# octanis_eps_revised.net
KiCad netlist of a schematic drawn in EAGLE
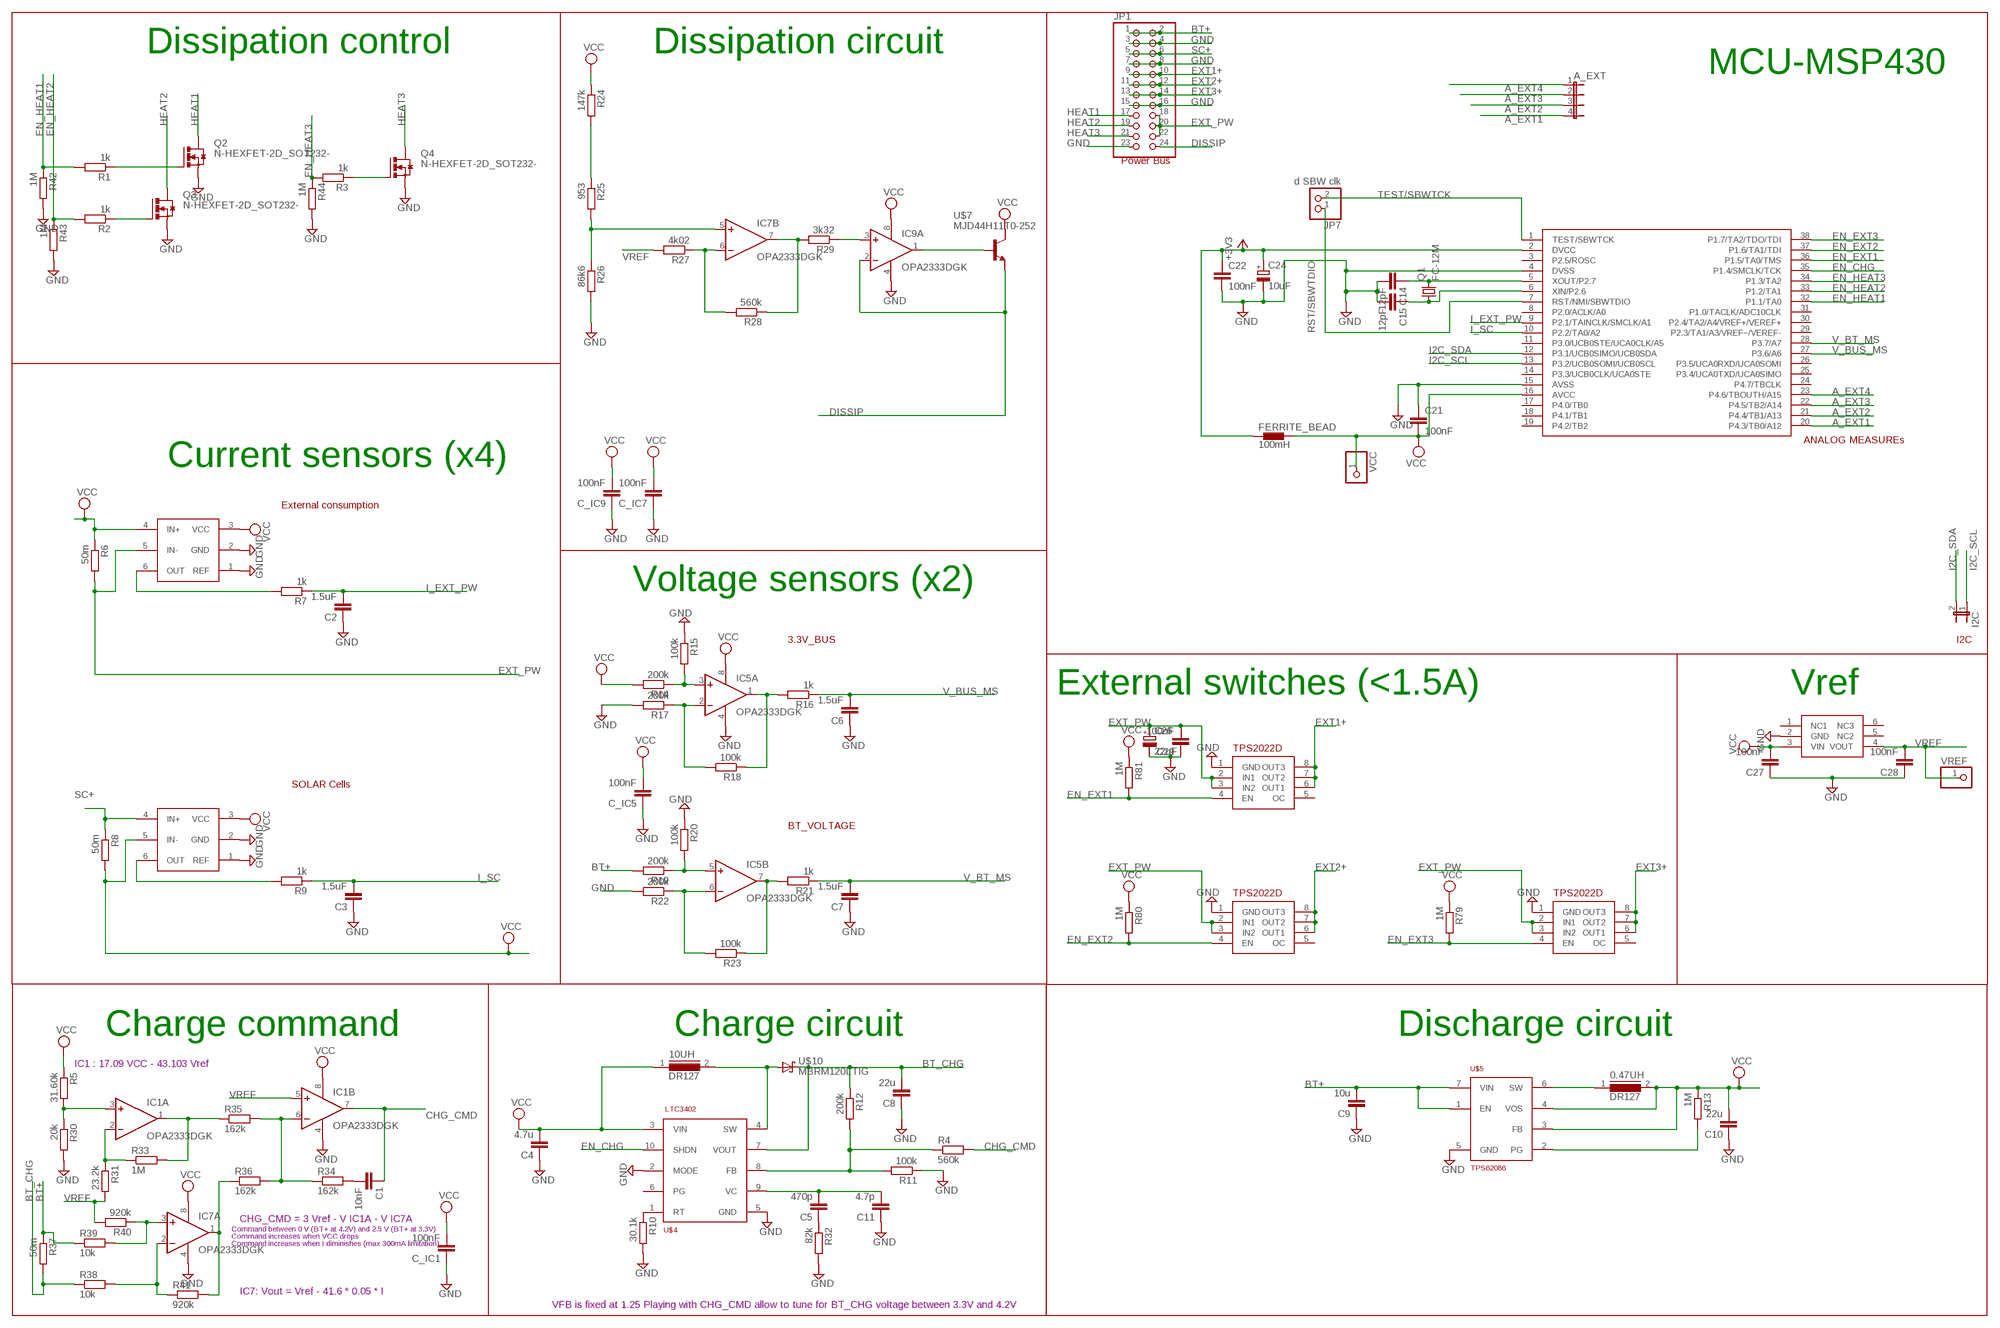
[diagram p0: schematic, sheet 1]

(export (version "E")
  (design (tool "Eeschema 10.0.6"))
  (components
    (comp (ref "0.47UH")
      (value "DR127")
      (footprint "eagle-import:DR127")
      (libsource (lib "eagle-import") (part "DR127"))
    )
    (comp (ref "10UH")
      (value "DR127")
      (footprint "eagle-import:DR127")
      (libsource (lib "eagle-import") (part "DR127"))
    )
    (comp (ref "A_EXT")
      (value "JP4E")
      (footprint "eagle-import:JP4")
      (libsource (lib "eagle-import") (part "JP4E"))
    )
    (comp (ref "C1")
      (value "10nF")
      (footprint "eagle-import:C0603")
      (libsource (lib "eagle-import") (part "C-EUC0603"))
    )
    (comp (ref "C2")
      (value "1.5uF")
      (footprint "eagle-import:C0603")
      (libsource (lib "eagle-import") (part "C-EUC0603"))
    )
    (comp (ref "C3")
      (value "1.5uF")
      (footprint "eagle-import:C0603")
      (libsource (lib "eagle-import") (part "C-EUC0603"))
    )
    (comp (ref "C4")
      (value "4.7u")
      (footprint "eagle-import:C1206")
      (libsource (lib "eagle-import") (part "C-EUC1206"))
    )
    (comp (ref "C5")
      (value "470p")
      (footprint "eagle-import:C0603")
      (libsource (lib "eagle-import") (part "C-EUC0603"))
    )
    (comp (ref "C6")
      (value "1.5uF")
      (footprint "eagle-import:C0603")
      (libsource (lib "eagle-import") (part "C-EUC0603"))
    )
    (comp (ref "C7")
      (value "1.5uF")
      (footprint "eagle-import:C0603")
      (libsource (lib "eagle-import") (part "C-EUC0603"))
    )
    (comp (ref "C8")
      (value "22u")
      (footprint "eagle-import:C0603")
      (libsource (lib "eagle-import") (part "C-EUC0603"))
    )
    (comp (ref "C9")
      (value "10u")
      (footprint "eagle-import:C1206")
      (libsource (lib "eagle-import") (part "C-EUC1206"))
    )
    (comp (ref "C10")
      (value "22u")
      (footprint "eagle-import:C1206")
      (libsource (lib "eagle-import") (part "C-EUC1206"))
    )
    (comp (ref "C11")
      (value "4.7p")
      (footprint "eagle-import:C0603")
      (libsource (lib "eagle-import") (part "C-EUC0603"))
    )
    (comp (ref "C14")
      (value "12pF")
      (footprint "eagle-import:C0603")
      (libsource (lib "eagle-import") (part "C-EUC0603"))
    )
    (comp (ref "C15")
      (value "12pF")
      (footprint "eagle-import:C0603")
      (libsource (lib "eagle-import") (part "C-EUC0603"))
    )
    (comp (ref "C21")
      (value "100nF")
      (footprint "eagle-import:C0603")
      (libsource (lib "eagle-import") (part "C-EUC0603"))
    )
    (comp (ref "C22")
      (value "100nF")
      (footprint "eagle-import:C0603")
      (libsource (lib "eagle-import") (part "C-EUC0603"))
    )
    (comp (ref "C24")
      (value "10uF")
      (footprint "eagle-import:A_3216-18R")
      (libsource (lib "eagle-import") (part "CPOL-EUA/3216-18R"))
    )
    (comp (ref "C26")
      (value "22uF")
      (footprint "eagle-import:A_3216-18R")
      (libsource (lib "eagle-import") (part "CPOL-EUA/3216-18R"))
    )
    (comp (ref "C27")
      (value "100nF")
      (footprint "eagle-import:C0603")
      (libsource (lib "eagle-import") (part "C-EUC0603"))
    )
    (comp (ref "C28")
      (value "100nF")
      (footprint "eagle-import:C0603")
      (libsource (lib "eagle-import") (part "C-EUC0603"))
    )
    (comp (ref "C29")
      (value "100nF")
      (footprint "eagle-import:C0603")
      (libsource (lib "eagle-import") (part "C-EUC0603"))
    )
    (comp (ref "C_IC1")
      (value "100nF")
      (footprint "eagle-import:C0603")
      (libsource (lib "eagle-import") (part "C-EUC0603"))
    )
    (comp (ref "C_IC5")
      (value "100nF")
      (footprint "eagle-import:C0603")
      (libsource (lib "eagle-import") (part "C-EUC0603"))
    )
    (comp (ref "C_IC7")
      (value "100nF")
      (footprint "eagle-import:C0603")
      (libsource (lib "eagle-import") (part "C-EUC0603"))
    )
    (comp (ref "C_IC9")
      (value "100nF")
      (footprint "eagle-import:C0603")
      (libsource (lib "eagle-import") (part "C-EUC0603"))
    )
    (comp (ref "FERRITE_BEAD")
      (value "100mH")
      (footprint "eagle-import:0402")
      (libsource (lib "eagle-import") (part "BLM15HD601SN1"))
    )
    (comp (ref "I2C")
      (value "JP1E")
      (footprint "eagle-import:JP1")
      (libsource (lib "eagle-import") (part "JP1E"))
    )
    (comp (ref "IC1")
      (value "OPA2333DGK")
      (footprint "eagle-import:MSOP08")
      (libsource (lib "eagle-import") (part "OPA2333DGK"))
    )
    (comp (ref "IC5")
      (value "OPA2333DGK")
      (footprint "eagle-import:MSOP08")
      (libsource (lib "eagle-import") (part "OPA2333DGK"))
    )
    (comp (ref "IC7")
      (value "OPA2333DGK")
      (footprint "eagle-import:MSOP08")
      (libsource (lib "eagle-import") (part "OPA2333DGK"))
    )
    (comp (ref "IC9")
      (value "OPA2333DGK")
      (footprint "eagle-import:MSOP08")
      (libsource (lib "eagle-import") (part "OPA2333DGK"))
    )
    (comp (ref "JP1")
      (value "PINHD-2X12")
      (footprint "eagle-import:2X12")
      (libsource (lib "eagle-import") (part "PINHD-2X12"))
    )
    (comp (ref "JP7")
      (value "d SBW clk")
      (footprint "eagle-import:1X02")
      (libsource (lib "eagle-import") (part "PINHD-1X2"))
    )
    (comp (ref "Q1")
      (value "FC-12M")
      (footprint "eagle-import:FC-12M")
      (libsource (lib "eagle-import") (part "FC-12M"))
    )
    (comp (ref "Q2")
      (value "N-HEXFET-2D_SOT232-")
      (footprint "eagle-import:SOT223")
      (libsource (lib "eagle-import") (part "N-HEXFET-2D_?-SOT232"))
    )
    (comp (ref "Q3")
      (value "N-HEXFET-2D_SOT232-")
      (footprint "eagle-import:SOT223")
      (libsource (lib "eagle-import") (part "N-HEXFET-2D_?-SOT232"))
    )
    (comp (ref "Q4")
      (value "N-HEXFET-2D_SOT232-")
      (footprint "eagle-import:SOT223")
      (libsource (lib "eagle-import") (part "N-HEXFET-2D_?-SOT232"))
    )
    (comp (ref "R1")
      (value "1k")
      (footprint "eagle-import:R0603")
      (libsource (lib "eagle-import") (part "R-EU_R0603"))
    )
    (comp (ref "R2")
      (value "1k")
      (footprint "eagle-import:R0603")
      (libsource (lib "eagle-import") (part "R-EU_R0603"))
    )
    (comp (ref "R3")
      (value "1k")
      (footprint "eagle-import:R0603")
      (libsource (lib "eagle-import") (part "R-EU_R0603"))
    )
    (comp (ref "R4")
      (value "560k")
      (footprint "eagle-import:R0603")
      (libsource (lib "eagle-import") (part "R-EU_R0603"))
    )
    (comp (ref "R5")
      (value "31.60k")
      (footprint "eagle-import:R0603")
      (libsource (lib "eagle-import") (part "R-EU_R0603"))
    )
    (comp (ref "R6")
      (value "50m")
      (footprint "eagle-import:R1206")
      (libsource (lib "eagle-import") (part "R-EU_R1206"))
    )
    (comp (ref "R7")
      (value "1k")
      (footprint "eagle-import:R0603")
      (libsource (lib "eagle-import") (part "R-EU_R0603"))
    )
    (comp (ref "R8")
      (value "50m")
      (footprint "eagle-import:R1206")
      (libsource (lib "eagle-import") (part "R-EU_R1206"))
    )
    (comp (ref "R9")
      (value "1k")
      (footprint "eagle-import:R0603")
      (libsource (lib "eagle-import") (part "R-EU_R0603"))
    )
    (comp (ref "R10")
      (value "30.1k")
      (footprint "eagle-import:R0603")
      (libsource (lib "eagle-import") (part "R-EU_R0603"))
    )
    (comp (ref "R11")
      (value "100k")
      (footprint "eagle-import:R0603")
      (libsource (lib "eagle-import") (part "R-EU_R0603"))
    )
    (comp (ref "R12")
      (value "200k")
      (footprint "eagle-import:R0603")
      (libsource (lib "eagle-import") (part "R-EU_R0603"))
    )
    (comp (ref "R13")
      (value "1M")
      (footprint "eagle-import:R0603")
      (libsource (lib "eagle-import") (part "R-EU_R0603"))
    )
    (comp (ref "R14")
      (value "200k")
      (footprint "eagle-import:R0603")
      (libsource (lib "eagle-import") (part "R-EU_R0603"))
    )
    (comp (ref "R15")
      (value "100k")
      (footprint "eagle-import:R0603")
      (libsource (lib "eagle-import") (part "R-EU_R0603"))
    )
    (comp (ref "R16")
      (value "1k")
      (footprint "eagle-import:R0603")
      (libsource (lib "eagle-import") (part "R-EU_R0603"))
    )
    (comp (ref "R17")
      (value "200k")
      (footprint "eagle-import:R0603")
      (libsource (lib "eagle-import") (part "R-EU_R0603"))
    )
    (comp (ref "R18")
      (value "100k")
      (footprint "eagle-import:R0603")
      (libsource (lib "eagle-import") (part "R-EU_R0603"))
    )
    (comp (ref "R19")
      (value "200k")
      (footprint "eagle-import:R0603")
      (libsource (lib "eagle-import") (part "R-EU_R0603"))
    )
    (comp (ref "R20")
      (value "100k")
      (footprint "eagle-import:R0603")
      (libsource (lib "eagle-import") (part "R-EU_R0603"))
    )
    (comp (ref "R21")
      (value "1k")
      (footprint "eagle-import:R0603")
      (libsource (lib "eagle-import") (part "R-EU_R0603"))
    )
    (comp (ref "R22")
      (value "200k")
      (footprint "eagle-import:R0603")
      (libsource (lib "eagle-import") (part "R-EU_R0603"))
    )
    (comp (ref "R23")
      (value "100k")
      (footprint "eagle-import:R0603")
      (libsource (lib "eagle-import") (part "R-EU_R0603"))
    )
    (comp (ref "R24")
      (value "147k")
      (footprint "eagle-import:R0603")
      (libsource (lib "eagle-import") (part "R-EU_R0603"))
    )
    (comp (ref "R25")
      (value "953")
      (footprint "eagle-import:R0603")
      (libsource (lib "eagle-import") (part "R-EU_R0603"))
    )
    (comp (ref "R26")
      (value "86k6")
      (footprint "eagle-import:R0603")
      (libsource (lib "eagle-import") (part "R-EU_R0603"))
    )
    (comp (ref "R27")
      (value "4k02")
      (footprint "eagle-import:R0603")
      (libsource (lib "eagle-import") (part "R-EU_R0603"))
    )
    (comp (ref "R28")
      (value "560k")
      (footprint "eagle-import:R0603")
      (libsource (lib "eagle-import") (part "R-EU_R0603"))
    )
    (comp (ref "R29")
      (value "3k32")
      (footprint "eagle-import:R0603")
      (libsource (lib "eagle-import") (part "R-EU_R0603"))
    )
    (comp (ref "R30")
      (value "20k")
      (footprint "eagle-import:R0603")
      (libsource (lib "eagle-import") (part "R-EU_R0603"))
    )
    (comp (ref "R31")
      (value "23.2k")
      (footprint "eagle-import:R0603")
      (libsource (lib "eagle-import") (part "R-EU_R0603"))
    )
    (comp (ref "R32")
      (value "82k")
      (footprint "eagle-import:R0603")
      (libsource (lib "eagle-import") (part "R-EU_R0603"))
    )
    (comp (ref "R33")
      (value "1M")
      (footprint "eagle-import:R0603")
      (libsource (lib "eagle-import") (part "R-EU_R0603"))
    )
    (comp (ref "R34")
      (value "162k")
      (footprint "eagle-import:R0603")
      (libsource (lib "eagle-import") (part "R-EU_R0603"))
    )
    (comp (ref "R35")
      (value "162k")
      (footprint "eagle-import:R0603")
      (libsource (lib "eagle-import") (part "R-EU_R0603"))
    )
    (comp (ref "R36")
      (value "162k")
      (footprint "eagle-import:R0603")
      (libsource (lib "eagle-import") (part "R-EU_R0603"))
    )
    (comp (ref "R37")
      (value "50m")
      (footprint "eagle-import:R1206")
      (libsource (lib "eagle-import") (part "R-EU_R1206"))
    )
    (comp (ref "R38")
      (value "10k")
      (footprint "eagle-import:R0603")
      (libsource (lib "eagle-import") (part "R-EU_R0603"))
    )
    (comp (ref "R39")
      (value "10k")
      (footprint "eagle-import:R0603")
      (libsource (lib "eagle-import") (part "R-EU_R0603"))
    )
    (comp (ref "R40")
      (value "920k")
      (footprint "eagle-import:R0603")
      (libsource (lib "eagle-import") (part "R-EU_R0603"))
    )
    (comp (ref "R41")
      (value "920k")
      (footprint "eagle-import:R0603")
      (libsource (lib "eagle-import") (part "R-EU_R0603"))
    )
    (comp (ref "R42")
      (value "1M")
      (footprint "eagle-import:R0603")
      (libsource (lib "eagle-import") (part "R-EU_R0603"))
    )
    (comp (ref "R43")
      (value "1M")
      (footprint "eagle-import:R0603")
      (libsource (lib "eagle-import") (part "R-EU_R0603"))
    )
    (comp (ref "R44")
      (value "1M")
      (footprint "eagle-import:R0603")
      (libsource (lib "eagle-import") (part "R-EU_R0603"))
    )
    (comp (ref "R79")
      (value "1M")
      (footprint "eagle-import:R0603")
      (libsource (lib "eagle-import") (part "R-EU_R0603"))
    )
    (comp (ref "R80")
      (value "1M")
      (footprint "eagle-import:R0603")
      (libsource (lib "eagle-import") (part "R-EU_R0603"))
    )
    (comp (ref "R81")
      (value "1M")
      (footprint "eagle-import:R0603")
      (libsource (lib "eagle-import") (part "R-EU_R0603"))
    )
    (comp (ref "U$2")
      (value "INA213")
      (footprint "eagle-import:SC70-6")
      (libsource (lib "eagle-import") (part "INA213"))
    )
    (comp (ref "U$3")
      (value "INA213")
      (footprint "eagle-import:SC70-6")
      (libsource (lib "eagle-import") (part "INA213"))
    )
    (comp (ref "U$4")
      (value "LTC3402")
      (footprint "eagle-import:MSOP10")
      (libsource (lib "eagle-import") (part "LTC3402"))
    )
    (comp (ref "U$5")
      (value "TPS62086")
      (footprint "eagle-import:QFN-7")
      (libsource (lib "eagle-import") (part "TPS62086"))
    )
    (comp (ref "U$6")
      (value "MSP430G2544")
      (footprint "eagle-import:TSSOP38")
      (libsource (lib "eagle-import") (part "MSP430G2544"))
    )
    (comp (ref "U$7")
      (value "MJD44H11T0-252")
      (footprint "eagle-import:TO252")
      (libsource (lib "eagle-import") (part "MJD44H11T0-252"))
    )
    (comp (ref "U$10")
      (value "MBRM120LTIG")
      (footprint "eagle-import:DO216AA")
      (libsource (lib "eagle-import") (part "MBRM120LTIG"))
    )
    (comp (ref "U$16")
      (value "TPS2022D")
      (footprint "eagle-import:SO8")
      (libsource (lib "eagle-import") (part "TPS2022D"))
    )
    (comp (ref "U$17")
      (value "TPS2022D")
      (footprint "eagle-import:SO8")
      (libsource (lib "eagle-import") (part "TPS2022D"))
    )
    (comp (ref "U$18")
      (value "TPS2022D")
      (footprint "eagle-import:SO8")
      (libsource (lib "eagle-import") (part "TPS2022D"))
    )
    (comp (ref "U$19")
      (value "ADR127B")
      (footprint "eagle-import:TSOT23-6")
      (libsource (lib "eagle-import") (part "ADR127B"))
    )
    (comp (ref "VCC")
      (value "PINHD-1X1")
      (footprint "eagle-import:1X01")
      (libsource (lib "eagle-import") (part "PINHD-1X1"))
    )
    (comp (ref "VREF")
      (value "PINHD-1X1")
      (footprint "eagle-import:1X01")
      (libsource (lib "eagle-import") (part "PINHD-1X1"))
    )
  )
  (nets
    (net (code "1") (name "+3V3") (class "Default")
      (node (ref "C22") (pin "1") (pinfunction "1_1") (pintype "passive"))
      (node (ref "C24") (pin "+") (pinfunction "+_+") (pintype "passive"))
      (node (ref "FERRITE_BEAD") (pin "1") (pinfunction "1_1") (pintype "passive"))
      (node (ref "U$6") (pin "2") (pinfunction "DVCC_2") (pintype "bidirectional"))
    )
    (net (code "2") (name "/A_EXT1") (class "Default")
      (node (ref "A_EXT") (pin "4") (pinfunction "4_4") (pintype "passive"))
      (node (ref "U$6") (pin "20") (pinfunction "P4.3/TB0/A12_20") (pintype "bidirectional"))
    )
    (net (code "3") (name "/A_EXT2") (class "Default")
      (node (ref "A_EXT") (pin "3") (pinfunction "3_3") (pintype "passive"))
      (node (ref "U$6") (pin "21") (pinfunction "P4.4/TB1/A13_21") (pintype "bidirectional"))
    )
    (net (code "4") (name "/A_EXT3") (class "Default")
      (node (ref "A_EXT") (pin "2") (pinfunction "2_2") (pintype "passive"))
      (node (ref "U$6") (pin "22") (pinfunction "P4.5/TB2/A14_22") (pintype "bidirectional"))
    )
    (net (code "5") (name "/A_EXT4") (class "Default")
      (node (ref "A_EXT") (pin "1") (pinfunction "1_1") (pintype "passive"))
      (node (ref "U$6") (pin "23") (pinfunction "P4.6/TBOUTH/A15_23") (pintype "bidirectional"))
    )
    (net (code "6") (name "/BT+") (class "Default")
      (node (ref "C9") (pin "2") (pinfunction "2_2") (pintype "passive"))
      (node (ref "JP1") (pin "1") (pinfunction "1_1") (pintype "passive"))
      (node (ref "JP1") (pin "2") (pinfunction "2_2") (pintype "passive"))
      (node (ref "R19") (pin "2") (pinfunction "2_2") (pintype "passive"))
      (node (ref "R37") (pin "1") (pinfunction "1_1") (pintype "passive"))
      (node (ref "R39") (pin "1") (pinfunction "1_1") (pintype "passive"))
      (node (ref "U$5") (pin "1") (pinfunction "EN_1") (pintype "bidirectional"))
      (node (ref "U$5") (pin "7") (pinfunction "VIN_7") (pintype "bidirectional"))
    )
    (net (code "7") (name "/BT_CHG") (class "Default")
      (node (ref "C8") (pin "2") (pinfunction "2_2") (pintype "passive"))
      (node (ref "R12") (pin "1") (pinfunction "1_1") (pintype "passive"))
      (node (ref "R37") (pin "2") (pinfunction "2_2") (pintype "passive"))
      (node (ref "R38") (pin "1") (pinfunction "1_1") (pintype "passive"))
      (node (ref "U$10") (pin "C") (pinfunction "K_C") (pintype "passive"))
      (node (ref "U$4") (pin "7") (pinfunction "VOUT_7") (pintype "bidirectional"))
    )
    (net (code "8") (name "/CHG_CMD") (class "Default")
      (node (ref "C1") (pin "1") (pinfunction "1_1") (pintype "passive"))
      (node (ref "IC1") (pin "7") (pinfunction "OUT_7") (pintype "output"))
      (node (ref "R4") (pin "2") (pinfunction "2_2") (pintype "passive"))
    )
    (net (code "9") (name "/DISSIP") (class "Default")
      (node (ref "IC9") (pin "2") (pinfunction "-IN_2") (pintype "input"))
      (node (ref "JP1") (pin "24") (pinfunction "24_24") (pintype "passive"))
      (node (ref "U$7") (pin "3") (pinfunction "E_3") (pintype "passive"))
    )
    (net (code "10") (name "/EN_CHG") (class "Default")
      (node (ref "U$4") (pin "10") (pinfunction "SHDN_10") (pintype "bidirectional"))
      (node (ref "U$6") (pin "35") (pinfunction "P1.4/SMCLK/TCK_35") (pintype "bidirectional"))
    )
    (net (code "11") (name "/EN_EXT1") (class "Default")
      (node (ref "R81") (pin "2") (pinfunction "2_2") (pintype "passive"))
      (node (ref "U$16") (pin "4") (pinfunction "EN_4") (pintype "bidirectional"))
      (node (ref "U$6") (pin "36") (pinfunction "P1.5/TA0/TMS_36") (pintype "bidirectional"))
    )
    (net (code "12") (name "/EN_EXT2") (class "Default")
      (node (ref "R80") (pin "2") (pinfunction "2_2") (pintype "passive"))
      (node (ref "U$17") (pin "4") (pinfunction "EN_4") (pintype "bidirectional"))
      (node (ref "U$6") (pin "37") (pinfunction "P1.6/TA1/TDI_37") (pintype "bidirectional"))
    )
    (net (code "13") (name "/EN_EXT3") (class "Default")
      (node (ref "R79") (pin "2") (pinfunction "2_2") (pintype "passive"))
      (node (ref "U$18") (pin "4") (pinfunction "EN_4") (pintype "bidirectional"))
      (node (ref "U$6") (pin "38") (pinfunction "P1.7/TA2/TDO/TDI_38") (pintype "bidirectional"))
    )
    (net (code "14") (name "/EN_HEAT1") (class "Default")
      (node (ref "R1") (pin "2") (pinfunction "2_2") (pintype "passive"))
      (node (ref "R42") (pin "1") (pinfunction "1_1") (pintype "passive"))
      (node (ref "U$6") (pin "32") (pinfunction "P1.1/TA0_32") (pintype "bidirectional"))
    )
    (net (code "15") (name "/EN_HEAT2") (class "Default")
      (node (ref "R2") (pin "2") (pinfunction "2_2") (pintype "passive"))
      (node (ref "R43") (pin "1") (pinfunction "1_1") (pintype "passive"))
      (node (ref "U$6") (pin "33") (pinfunction "P1.2/TA1_33") (pintype "bidirectional"))
    )
    (net (code "16") (name "/EN_HEAT3") (class "Default")
      (node (ref "R3") (pin "2") (pinfunction "2_2") (pintype "passive"))
      (node (ref "R44") (pin "1") (pinfunction "1_1") (pintype "passive"))
      (node (ref "U$6") (pin "34") (pinfunction "P1.3/TA2_34") (pintype "bidirectional"))
    )
    (net (code "17") (name "/EXT1+") (class "Default")
      (node (ref "JP1") (pin "10") (pinfunction "10_10") (pintype "passive"))
      (node (ref "JP1") (pin "9") (pinfunction "9_9") (pintype "passive"))
      (node (ref "U$16") (pin "6") (pinfunction "OUT1_6") (pintype "bidirectional"))
      (node (ref "U$16") (pin "7") (pinfunction "OUT2_7") (pintype "bidirectional"))
      (node (ref "U$16") (pin "8") (pinfunction "OUT3_8") (pintype "bidirectional"))
    )
    (net (code "18") (name "/EXT2+") (class "Default")
      (node (ref "JP1") (pin "11") (pinfunction "11_11") (pintype "passive"))
      (node (ref "JP1") (pin "12") (pinfunction "12_12") (pintype "passive"))
      (node (ref "U$17") (pin "6") (pinfunction "OUT1_6") (pintype "bidirectional"))
      (node (ref "U$17") (pin "7") (pinfunction "OUT2_7") (pintype "bidirectional"))
      (node (ref "U$17") (pin "8") (pinfunction "OUT3_8") (pintype "bidirectional"))
    )
    (net (code "19") (name "/EXT3+") (class "Default")
      (node (ref "JP1") (pin "13") (pinfunction "13_13") (pintype "passive"))
      (node (ref "JP1") (pin "14") (pinfunction "14_14") (pintype "passive"))
      (node (ref "U$18") (pin "6") (pinfunction "OUT1_6") (pintype "bidirectional"))
      (node (ref "U$18") (pin "7") (pinfunction "OUT2_7") (pintype "bidirectional"))
      (node (ref "U$18") (pin "8") (pinfunction "OUT3_8") (pintype "bidirectional"))
    )
    (net (code "20") (name "/EXT_PW") (class "Default")
      (node (ref "C26") (pin "+") (pinfunction "+_+") (pintype "passive"))
      (node (ref "C29") (pin "2") (pinfunction "2_2") (pintype "passive"))
      (node (ref "JP1") (pin "18") (pinfunction "18_18") (pintype "passive"))
      (node (ref "JP1") (pin "20") (pinfunction "20_20") (pintype "passive"))
      (node (ref "JP1") (pin "22") (pinfunction "22_22") (pintype "passive"))
      (node (ref "R6") (pin "2") (pinfunction "2_2") (pintype "passive"))
      (node (ref "U$16") (pin "2") (pinfunction "IN1_2") (pintype "bidirectional"))
      (node (ref "U$16") (pin "3") (pinfunction "IN2_3") (pintype "bidirectional"))
      (node (ref "U$17") (pin "2") (pinfunction "IN1_2") (pintype "bidirectional"))
      (node (ref "U$17") (pin "3") (pinfunction "IN2_3") (pintype "bidirectional"))
      (node (ref "U$18") (pin "2") (pinfunction "IN1_2") (pintype "bidirectional"))
      (node (ref "U$18") (pin "3") (pinfunction "IN2_3") (pintype "bidirectional"))
      (node (ref "U$2") (pin "5") (pinfunction "IN-_5") (pintype "bidirectional"))
    )
    (net (code "21") (name "/HEAT1") (class "Default")
      (node (ref "JP1") (pin "17") (pinfunction "17_17") (pintype "passive"))
      (node (ref "Q2") (pin "2") (pinfunction "D_2") (pintype "passive"))
      (node (ref "Q2") (pin "4") (pinfunction "D_4") (pintype "passive"))
    )
    (net (code "22") (name "/HEAT2") (class "Default")
      (node (ref "JP1") (pin "19") (pinfunction "19_19") (pintype "passive"))
      (node (ref "Q3") (pin "2") (pinfunction "D_2") (pintype "passive"))
      (node (ref "Q3") (pin "4") (pinfunction "D_4") (pintype "passive"))
    )
    (net (code "23") (name "/HEAT3") (class "Default")
      (node (ref "JP1") (pin "21") (pinfunction "21_21") (pintype "passive"))
      (node (ref "Q4") (pin "2") (pinfunction "D_2") (pintype "passive"))
      (node (ref "Q4") (pin "4") (pinfunction "D_4") (pintype "passive"))
    )
    (net (code "24") (name "/I2C_SCL") (class "Default")
      (node (ref "I2C") (pin "1") (pinfunction "1_1") (pintype "passive"))
      (node (ref "U$6") (pin "13") (pinfunction "P3.2/UCB0SOMI/UCB0SCL_13") (pintype "bidirectional"))
    )
    (net (code "25") (name "/I2C_SDA") (class "Default")
      (node (ref "I2C") (pin "2") (pinfunction "2_2") (pintype "passive"))
      (node (ref "U$6") (pin "12") (pinfunction "P3.1/UCB0SIMO/UCB0SDA_12") (pintype "bidirectional"))
    )
    (net (code "26") (name "/I_EXT_PW") (class "Default")
      (node (ref "C2") (pin "2") (pinfunction "2_2") (pintype "passive"))
      (node (ref "R7") (pin "1") (pinfunction "1_1") (pintype "passive"))
      (node (ref "U$6") (pin "9") (pinfunction "P2.1/TAINCLK/SMCLK/A1_9") (pintype "bidirectional"))
    )
    (net (code "27") (name "/I_SC") (class "Default")
      (node (ref "C3") (pin "2") (pinfunction "2_2") (pintype "passive"))
      (node (ref "R9") (pin "1") (pinfunction "1_1") (pintype "passive"))
      (node (ref "U$6") (pin "10") (pinfunction "P2.2/TA0/A2_10") (pintype "bidirectional"))
    )
    (net (code "28") (name "/RST{slash}SBWTDIO") (class "Default")
      (node (ref "JP7") (pin "1") (pinfunction "1_1") (pintype "passive"))
      (node (ref "U$6") (pin "7") (pinfunction "RST/NMI/SBWTDIO_7") (pintype "bidirectional"))
    )
    (net (code "29") (name "/SC+") (class "Default")
      (node (ref "JP1") (pin "5") (pinfunction "5_5") (pintype "passive"))
      (node (ref "JP1") (pin "6") (pinfunction "6_6") (pintype "passive"))
      (node (ref "R8") (pin "1") (pinfunction "1_1") (pintype "passive"))
      (node (ref "U$3") (pin "4") (pinfunction "IN+_4") (pintype "bidirectional"))
    )
    (net (code "30") (name "/TEST{slash}SBWTCK") (class "Default")
      (node (ref "JP7") (pin "2") (pinfunction "2_2") (pintype "passive"))
      (node (ref "U$6") (pin "1") (pinfunction "TEST/SBWTCK_1") (pintype "bidirectional"))
    )
    (net (code "31") (name "/VREF") (class "Default")
      (node (ref "C28") (pin "2") (pinfunction "2_2") (pintype "passive"))
      (node (ref "IC1") (pin "5") (pinfunction "+IN_5") (pintype "input"))
      (node (ref "R27") (pin "2") (pinfunction "2_2") (pintype "passive"))
      (node (ref "R31") (pin "2") (pinfunction "2_2") (pintype "passive"))
      (node (ref "R40") (pin "2") (pinfunction "2_2") (pintype "passive"))
      (node (ref "U$19") (pin "4") (pinfunction "VOUT_4") (pintype "bidirectional"))
      (node (ref "VREF") (pin "1") (pinfunction "1_1") (pintype "passive"))
    )
    (net (code "32") (name "/V_BT_MS") (class "Default")
      (node (ref "C7") (pin "2") (pinfunction "2_2") (pintype "passive"))
      (node (ref "R21") (pin "1") (pinfunction "1_1") (pintype "passive"))
      (node (ref "U$6") (pin "28") (pinfunction "P3.7/A7_28") (pintype "bidirectional"))
    )
    (net (code "33") (name "/V_BUS_MS") (class "Default")
      (node (ref "C6") (pin "2") (pinfunction "2_2") (pintype "passive"))
      (node (ref "R16") (pin "1") (pinfunction "1_1") (pintype "passive"))
      (node (ref "U$6") (pin "27") (pinfunction "P3.6/A6_27") (pintype "bidirectional"))
    )
    (net (code "34") (name "GND") (class "Default")
      (node (ref "C10") (pin "1") (pinfunction "1_1") (pintype "passive"))
      (node (ref "C11") (pin "1") (pinfunction "1_1") (pintype "passive"))
      (node (ref "C14") (pin "2") (pinfunction "2_2") (pintype "passive"))
      (node (ref "C15") (pin "2") (pinfunction "2_2") (pintype "passive"))
      (node (ref "C2") (pin "1") (pinfunction "1_1") (pintype "passive"))
      (node (ref "C21") (pin "1") (pinfunction "1_1") (pintype "passive"))
      (node (ref "C22") (pin "2") (pinfunction "2_2") (pintype "passive"))
      (node (ref "C24") (pin "-") (pinfunction "-_-") (pintype "passive"))
      (node (ref "C26") (pin "-") (pinfunction "-_-") (pintype "passive"))
      (node (ref "C27") (pin "1") (pinfunction "1_1") (pintype "passive"))
      (node (ref "C28") (pin "1") (pinfunction "1_1") (pintype "passive"))
      (node (ref "C29") (pin "1") (pinfunction "1_1") (pintype "passive"))
      (node (ref "C3") (pin "1") (pinfunction "1_1") (pintype "passive"))
      (node (ref "C4") (pin "1") (pinfunction "1_1") (pintype "passive"))
      (node (ref "C6") (pin "1") (pinfunction "1_1") (pintype "passive"))
      (node (ref "C7") (pin "1") (pinfunction "1_1") (pintype "passive"))
      (node (ref "C8") (pin "1") (pinfunction "1_1") (pintype "passive"))
      (node (ref "C9") (pin "1") (pinfunction "1_1") (pintype "passive"))
      (node (ref "C_IC1") (pin "1") (pinfunction "1_1") (pintype "passive"))
      (node (ref "C_IC5") (pin "1") (pinfunction "1_1") (pintype "passive"))
      (node (ref "C_IC7") (pin "1") (pinfunction "1_1") (pintype "passive"))
      (node (ref "C_IC9") (pin "1") (pinfunction "1_1") (pintype "passive"))
      (node (ref "IC1") (pin "4") (pinfunction "V-_4") (pintype "power_in"))
      (node (ref "IC5") (pin "4") (pinfunction "V-_4") (pintype "power_in"))
      (node (ref "IC7") (pin "4") (pinfunction "V-_4") (pintype "power_in"))
      (node (ref "IC9") (pin "4") (pinfunction "V-_4") (pintype "power_in"))
      (node (ref "JP1") (pin "15") (pinfunction "15_15") (pintype "passive"))
      (node (ref "JP1") (pin "16") (pinfunction "16_16") (pintype "passive"))
      (node (ref "JP1") (pin "23") (pinfunction "23_23") (pintype "passive"))
      (node (ref "JP1") (pin "3") (pinfunction "3_3") (pintype "passive"))
      (node (ref "JP1") (pin "4") (pinfunction "4_4") (pintype "passive"))
      (node (ref "JP1") (pin "7") (pinfunction "7_7") (pintype "passive"))
      (node (ref "JP1") (pin "8") (pinfunction "8_8") (pintype "passive"))
      (node (ref "Q2") (pin "3") (pinfunction "S_3") (pintype "passive"))
      (node (ref "Q3") (pin "3") (pinfunction "S_3") (pintype "passive"))
      (node (ref "Q4") (pin "3") (pinfunction "S_3") (pintype "passive"))
      (node (ref "R10") (pin "2") (pinfunction "2_2") (pintype "passive"))
      (node (ref "R11") (pin "1") (pinfunction "1_1") (pintype "passive"))
      (node (ref "R15") (pin "1") (pinfunction "1_1") (pintype "passive"))
      (node (ref "R17") (pin "2") (pinfunction "2_2") (pintype "passive"))
      (node (ref "R20") (pin "1") (pinfunction "1_1") (pintype "passive"))
      (node (ref "R22") (pin "2") (pinfunction "2_2") (pintype "passive"))
      (node (ref "R26") (pin "2") (pinfunction "2_2") (pintype "passive"))
      (node (ref "R30") (pin "2") (pinfunction "2_2") (pintype "passive"))
      (node (ref "R32") (pin "2") (pinfunction "2_2") (pintype "passive"))
      (node (ref "R42") (pin "2") (pinfunction "2_2") (pintype "passive"))
      (node (ref "R43") (pin "2") (pinfunction "2_2") (pintype "passive"))
      (node (ref "R44") (pin "2") (pinfunction "2_2") (pintype "passive"))
      (node (ref "U$16") (pin "1") (pinfunction "GND_1") (pintype "bidirectional"))
      (node (ref "U$17") (pin "1") (pinfunction "GND_1") (pintype "bidirectional"))
      (node (ref "U$18") (pin "1") (pinfunction "GND_1") (pintype "bidirectional"))
      (node (ref "U$19") (pin "2") (pinfunction "GND_2") (pintype "bidirectional"))
      (node (ref "U$2") (pin "1") (pinfunction "REF_1") (pintype "bidirectional"))
      (node (ref "U$2") (pin "2") (pinfunction "GND_2") (pintype "bidirectional"))
      (node (ref "U$3") (pin "1") (pinfunction "REF_1") (pintype "bidirectional"))
      (node (ref "U$3") (pin "2") (pinfunction "GND_2") (pintype "bidirectional"))
      (node (ref "U$4") (pin "2") (pinfunction "MODE_2") (pintype "bidirectional"))
      (node (ref "U$4") (pin "5") (pinfunction "GND_5") (pintype "bidirectional"))
      (node (ref "U$5") (pin "5") (pinfunction "GND_5") (pintype "bidirectional"))
      (node (ref "U$6") (pin "15") (pinfunction "AVSS_15") (pintype "bidirectional"))
      (node (ref "U$6") (pin "4") (pinfunction "DVSS_4") (pintype "bidirectional"))
    )
    (net (code "35") (name "Net-(C1-Pad2)") (class "Default")
      (node (ref "C1") (pin "2") (pinfunction "2_2") (pintype "passive"))
      (node (ref "R34") (pin "2") (pinfunction "2_2") (pintype "passive"))
    )
    (net (code "36") (name "Net-(C5-Pad1)") (class "Default")
      (node (ref "C5") (pin "1") (pinfunction "1_1") (pintype "passive"))
      (node (ref "R32") (pin "1") (pinfunction "1_1") (pintype "passive"))
    )
    (net (code "37") (name "Net-(IC1A-+IN)") (class "Default")
      (node (ref "IC1") (pin "3") (pinfunction "+IN_3") (pintype "input"))
      (node (ref "R30") (pin "1") (pinfunction "1_1") (pintype "passive"))
      (node (ref "R5") (pin "2") (pinfunction "2_2") (pintype "passive"))
    )
    (net (code "38") (name "Net-(IC1A--IN)") (class "Default")
      (node (ref "IC1") (pin "2") (pinfunction "-IN_2") (pintype "input"))
      (node (ref "R31") (pin "1") (pinfunction "1_1") (pintype "passive"))
      (node (ref "R33") (pin "1") (pinfunction "1_1") (pintype "passive"))
    )
    (net (code "39") (name "Net-(IC1A-OUT)") (class "Default")
      (node (ref "IC1") (pin "1") (pinfunction "OUT_1") (pintype "output"))
      (node (ref "R33") (pin "2") (pinfunction "2_2") (pintype "passive"))
      (node (ref "R35") (pin "1") (pinfunction "1_1") (pintype "passive"))
    )
    (net (code "40") (name "Net-(IC1B--IN)") (class "Default")
      (node (ref "IC1") (pin "6") (pinfunction "-IN_6") (pintype "input"))
      (node (ref "R34") (pin "1") (pinfunction "1_1") (pintype "passive"))
      (node (ref "R35") (pin "2") (pinfunction "2_2") (pintype "passive"))
      (node (ref "R36") (pin "2") (pinfunction "2_2") (pintype "passive"))
    )
    (net (code "41") (name "Net-(IC5A-+IN)") (class "Default")
      (node (ref "IC5") (pin "3") (pinfunction "+IN_3") (pintype "input"))
      (node (ref "R14") (pin "1") (pinfunction "1_1") (pintype "passive"))
      (node (ref "R15") (pin "2") (pinfunction "2_2") (pintype "passive"))
    )
    (net (code "42") (name "Net-(IC5A--IN)") (class "Default")
      (node (ref "IC5") (pin "2") (pinfunction "-IN_2") (pintype "input"))
      (node (ref "R17") (pin "1") (pinfunction "1_1") (pintype "passive"))
      (node (ref "R18") (pin "2") (pinfunction "2_2") (pintype "passive"))
    )
    (net (code "43") (name "Net-(IC5A-OUT)") (class "Default")
      (node (ref "IC5") (pin "1") (pinfunction "OUT_1") (pintype "output"))
      (node (ref "R16") (pin "2") (pinfunction "2_2") (pintype "passive"))
      (node (ref "R18") (pin "1") (pinfunction "1_1") (pintype "passive"))
    )
    (net (code "44") (name "Net-(IC5B-+IN)") (class "Default")
      (node (ref "IC5") (pin "5") (pinfunction "+IN_5") (pintype "input"))
      (node (ref "R19") (pin "1") (pinfunction "1_1") (pintype "passive"))
      (node (ref "R20") (pin "2") (pinfunction "2_2") (pintype "passive"))
    )
    (net (code "45") (name "Net-(IC5B--IN)") (class "Default")
      (node (ref "IC5") (pin "6") (pinfunction "-IN_6") (pintype "input"))
      (node (ref "R22") (pin "1") (pinfunction "1_1") (pintype "passive"))
      (node (ref "R23") (pin "2") (pinfunction "2_2") (pintype "passive"))
    )
    (net (code "46") (name "Net-(IC5B-OUT)") (class "Default")
      (node (ref "IC5") (pin "7") (pinfunction "OUT_7") (pintype "output"))
      (node (ref "R21") (pin "2") (pinfunction "2_2") (pintype "passive"))
      (node (ref "R23") (pin "1") (pinfunction "1_1") (pintype "passive"))
    )
    (net (code "47") (name "Net-(IC7A-+IN)") (class "Default")
      (node (ref "IC7") (pin "3") (pinfunction "+IN_3") (pintype "input"))
      (node (ref "R39") (pin "2") (pinfunction "2_2") (pintype "passive"))
      (node (ref "R40") (pin "1") (pinfunction "1_1") (pintype "passive"))
    )
    (net (code "48") (name "Net-(IC7A--IN)") (class "Default")
      (node (ref "IC7") (pin "2") (pinfunction "-IN_2") (pintype "input"))
      (node (ref "R38") (pin "2") (pinfunction "2_2") (pintype "passive"))
      (node (ref "R41") (pin "1") (pinfunction "1_1") (pintype "passive"))
    )
    (net (code "49") (name "Net-(IC7A-OUT)") (class "Default")
      (node (ref "IC7") (pin "1") (pinfunction "OUT_1") (pintype "output"))
      (node (ref "R36") (pin "1") (pinfunction "1_1") (pintype "passive"))
      (node (ref "R41") (pin "2") (pinfunction "2_2") (pintype "passive"))
    )
    (net (code "50") (name "Net-(IC7B-+IN)") (class "Default")
      (node (ref "IC7") (pin "5") (pinfunction "+IN_5") (pintype "input"))
      (node (ref "R25") (pin "2") (pinfunction "2_2") (pintype "passive"))
      (node (ref "R26") (pin "1") (pinfunction "1_1") (pintype "passive"))
    )
    (net (code "51") (name "Net-(IC7B--IN)") (class "Default")
      (node (ref "IC7") (pin "6") (pinfunction "-IN_6") (pintype "input"))
      (node (ref "R27") (pin "1") (pinfunction "1_1") (pintype "passive"))
      (node (ref "R28") (pin "2") (pinfunction "2_2") (pintype "passive"))
    )
    (net (code "52") (name "Net-(IC7B-OUT)") (class "Default")
      (node (ref "IC7") (pin "7") (pinfunction "OUT_7") (pintype "output"))
      (node (ref "R28") (pin "1") (pinfunction "1_1") (pintype "passive"))
      (node (ref "R29") (pin "2") (pinfunction "2_2") (pintype "passive"))
    )
    (net (code "53") (name "Net-(IC9A-+IN)") (class "Default")
      (node (ref "IC9") (pin "3") (pinfunction "+IN_3") (pintype "input"))
      (node (ref "R29") (pin "1") (pinfunction "1_1") (pintype "passive"))
    )
    (net (code "54") (name "Net-(IC9A-OUT)") (class "Default")
      (node (ref "IC9") (pin "1") (pinfunction "OUT_1") (pintype "output"))
      (node (ref "U$7") (pin "1") (pinfunction "B_1") (pintype "passive"))
    )
    (net (code "55") (name "Net-(Q2-G)") (class "Default")
      (node (ref "Q2") (pin "1") (pinfunction "G_1") (pintype "passive"))
      (node (ref "R1") (pin "1") (pinfunction "1_1") (pintype "passive"))
    )
    (net (code "56") (name "Net-(Q3-G)") (class "Default")
      (node (ref "Q3") (pin "1") (pinfunction "G_1") (pintype "passive"))
      (node (ref "R2") (pin "1") (pinfunction "1_1") (pintype "passive"))
    )
    (net (code "57") (name "Net-(Q4-G)") (class "Default")
      (node (ref "Q4") (pin "1") (pinfunction "G_1") (pintype "passive"))
      (node (ref "R3") (pin "1") (pinfunction "1_1") (pintype "passive"))
    )
    (net (code "58") (name "Net-(R24-Pad2)") (class "Default")
      (node (ref "R24") (pin "2") (pinfunction "2_2") (pintype "passive"))
      (node (ref "R25") (pin "1") (pinfunction "1_1") (pintype "passive"))
    )
    (net (code "59") (name "Net-(U$2-OUT)") (class "Default")
      (node (ref "R7") (pin "2") (pinfunction "2_2") (pintype "passive"))
      (node (ref "U$2") (pin "6") (pinfunction "OUT_6") (pintype "bidirectional"))
    )
    (net (code "60") (name "Net-(U$3-OUT)") (class "Default")
      (node (ref "R9") (pin "2") (pinfunction "2_2") (pintype "passive"))
      (node (ref "U$3") (pin "6") (pinfunction "OUT_6") (pintype "bidirectional"))
    )
    (net (code "61") (name "Net-(U$4-FB)") (class "Default")
      (node (ref "R11") (pin "2") (pinfunction "2_2") (pintype "passive"))
      (node (ref "R12") (pin "2") (pinfunction "2_2") (pintype "passive"))
      (node (ref "R4") (pin "1") (pinfunction "1_1") (pintype "passive"))
      (node (ref "U$4") (pin "8") (pinfunction "FB_8") (pintype "bidirectional"))
    )
    (net (code "62") (name "Net-(U$4-RT)") (class "Default")
      (node (ref "R10") (pin "1") (pinfunction "1_1") (pintype "passive"))
      (node (ref "U$4") (pin "1") (pinfunction "RT_1") (pintype "bidirectional"))
    )
    (net (code "63") (name "Net-(U$4-SW)") (class "Default")
      (node (ref "10UH") (pin "2") (pinfunction "2_2") (pintype "passive"))
      (node (ref "U$10") (pin "A") (pinfunction "A_A") (pintype "passive"))
      (node (ref "U$4") (pin "4") (pinfunction "SW_4") (pintype "bidirectional"))
    )
    (net (code "64") (name "Net-(U$4-VC)") (class "Default")
      (node (ref "C11") (pin "2") (pinfunction "2_2") (pintype "passive"))
      (node (ref "C5") (pin "2") (pinfunction "2_2") (pintype "passive"))
      (node (ref "U$4") (pin "9") (pinfunction "VC_9") (pintype "bidirectional"))
    )
    (net (code "65") (name "Net-(U$5-PG)") (class "Default")
      (node (ref "R13") (pin "2") (pinfunction "2_2") (pintype "passive"))
      (node (ref "U$5") (pin "2") (pinfunction "PG_2") (pintype "bidirectional"))
    )
    (net (code "66") (name "Net-(U$5-SW)") (class "Default")
      (node (ref "0.47UH") (pin "1") (pinfunction "1_1") (pintype "passive"))
      (node (ref "U$5") (pin "6") (pinfunction "SW_6") (pintype "bidirectional"))
    )
    (net (code "67") (name "Net-(U$6-XIN{slash}P2.6)") (class "Default")
      (node (ref "C15") (pin "1") (pinfunction "1_1") (pintype "passive"))
      (node (ref "Q1") (pin "1") (pinfunction "1_1") (pintype "passive"))
      (node (ref "U$6") (pin "6") (pinfunction "XIN/P2.6_6") (pintype "bidirectional"))
    )
    (net (code "68") (name "Net-(U$6-XOUT{slash}P2.7)") (class "Default")
      (node (ref "C14") (pin "1") (pinfunction "1_1") (pintype "passive"))
      (node (ref "Q1") (pin "2") (pinfunction "2_2") (pintype "passive"))
      (node (ref "U$6") (pin "5") (pinfunction "XOUT/P2.7_5") (pintype "bidirectional"))
    )
    (net (code "69") (name "VCC") (class "Default")
      (node (ref "0.47UH") (pin "2") (pinfunction "2_2") (pintype "passive"))
      (node (ref "10UH") (pin "1") (pinfunction "1_1") (pintype "passive"))
      (node (ref "C10") (pin "2") (pinfunction "2_2") (pintype "passive"))
      (node (ref "C21") (pin "2") (pinfunction "2_2") (pintype "passive"))
      (node (ref "C27") (pin "2") (pinfunction "2_2") (pintype "passive"))
      (node (ref "C4") (pin "2") (pinfunction "2_2") (pintype "passive"))
      (node (ref "C_IC1") (pin "2") (pinfunction "2_2") (pintype "passive"))
      (node (ref "C_IC5") (pin "2") (pinfunction "2_2") (pintype "passive"))
      (node (ref "C_IC7") (pin "2") (pinfunction "2_2") (pintype "passive"))
      (node (ref "C_IC9") (pin "2") (pinfunction "2_2") (pintype "passive"))
      (node (ref "FERRITE_BEAD") (pin "2") (pinfunction "2_2") (pintype "passive"))
      (node (ref "IC1") (pin "8") (pinfunction "V+_8") (pintype "power_in"))
      (node (ref "IC5") (pin "8") (pinfunction "V+_8") (pintype "power_in"))
      (node (ref "IC7") (pin "8") (pinfunction "V+_8") (pintype "power_in"))
      (node (ref "IC9") (pin "8") (pinfunction "V+_8") (pintype "power_in"))
      (node (ref "R13") (pin "1") (pinfunction "1_1") (pintype "passive"))
      (node (ref "R14") (pin "2") (pinfunction "2_2") (pintype "passive"))
      (node (ref "R24") (pin "1") (pinfunction "1_1") (pintype "passive"))
      (node (ref "R5") (pin "1") (pinfunction "1_1") (pintype "passive"))
      (node (ref "R6") (pin "1") (pinfunction "1_1") (pintype "passive"))
      (node (ref "R79") (pin "1") (pinfunction "1_1") (pintype "passive"))
      (node (ref "R8") (pin "2") (pinfunction "2_2") (pintype "passive"))
      (node (ref "R80") (pin "1") (pinfunction "1_1") (pintype "passive"))
      (node (ref "R81") (pin "1") (pinfunction "1_1") (pintype "passive"))
      (node (ref "U$19") (pin "3") (pinfunction "VIN_3") (pintype "bidirectional"))
      (node (ref "U$2") (pin "3") (pinfunction "VCC_3") (pintype "bidirectional"))
      (node (ref "U$2") (pin "4") (pinfunction "IN+_4") (pintype "bidirectional"))
      (node (ref "U$3") (pin "3") (pinfunction "VCC_3") (pintype "bidirectional"))
      (node (ref "U$3") (pin "5") (pinfunction "IN-_5") (pintype "bidirectional"))
      (node (ref "U$4") (pin "3") (pinfunction "VIN_3") (pintype "bidirectional"))
      (node (ref "U$5") (pin "3") (pinfunction "FB_3") (pintype "bidirectional"))
      (node (ref "U$5") (pin "4") (pinfunction "VOS_4") (pintype "bidirectional"))
      (node (ref "U$6") (pin "16") (pinfunction "AVCC_16") (pintype "bidirectional"))
      (node (ref "U$7") (pin "2") (pinfunction "C_2") (pintype "passive"))
      (node (ref "VCC") (pin "1") (pinfunction "1_1") (pintype "passive"))
    )
    (net (code "70") (name "unconnected-(U$4-PG-Pad6)") (class "Default")
      (node (ref "U$4") (pin "6") (pinfunction "PG_6") (pintype "bidirectional"))
    )
    (net (code "71") (name "unconnected-(U$6-P1.0{slash}TACLK{slash}ADC10CLK-Pad31)") (class "Default")
      (node (ref "U$6") (pin "31") (pinfunction "P1.0/TACLK/ADC10CLK_31") (pintype "bidirectional"))
    )
    (net (code "72") (name "unconnected-(U$6-P2.0{slash}ACLK{slash}A0-Pad8)") (class "Default")
      (node (ref "U$6") (pin "8") (pinfunction "P2.0/ACLK/A0_8") (pintype "bidirectional"))
    )
    (net (code "73") (name "unconnected-(U$6-P2.3{slash}TA1{slash}A3{slash}VREF−{slash}VEREF--Pad29)") (class "Default")
      (node (ref "U$6") (pin "29") (pinfunction "P2.3/TA1/A3/VREF−/VEREF-_29") (pintype "bidirectional"))
    )
    (net (code "74") (name "unconnected-(U$6-P2.4{slash}TA2{slash}A4{slash}VREF+{slash}VEREF+-Pad30)") (class "Default")
      (node (ref "U$6") (pin "30") (pinfunction "P2.4/TA2/A4/VREF+/VEREF+_30") (pintype "bidirectional"))
    )
    (net (code "75") (name "unconnected-(U$6-P2.5{slash}ROSC-Pad3)") (class "Default")
      (node (ref "U$6") (pin "3") (pinfunction "P2.5/ROSC_3") (pintype "bidirectional"))
    )
    (net (code "76") (name "unconnected-(U$6-P3.0{slash}UCB0STE{slash}UCA0CLK{slash}A5-Pad11)") (class "Default")
      (node (ref "U$6") (pin "11") (pinfunction "P3.0/UCB0STE/UCA0CLK/A5_11") (pintype "bidirectional"))
    )
    (net (code "77") (name "unconnected-(U$6-P3.3{slash}UCB0CLK{slash}UCA0STE-Pad14)") (class "Default")
      (node (ref "U$6") (pin "14") (pinfunction "P3.3/UCB0CLK/UCA0STE_14") (pintype "bidirectional"))
    )
    (net (code "78") (name "unconnected-(U$6-P3.4{slash}UCA0TXD{slash}UCA0SIMO-Pad25)") (class "Default")
      (node (ref "U$6") (pin "25") (pinfunction "P3.4/UCA0TXD/UCA0SIMO_25") (pintype "bidirectional"))
    )
    (net (code "79") (name "unconnected-(U$6-P3.5{slash}UCA0RXD{slash}UCA0SOMI-Pad26)") (class "Default")
      (node (ref "U$6") (pin "26") (pinfunction "P3.5/UCA0RXD/UCA0SOMI_26") (pintype "bidirectional"))
    )
    (net (code "80") (name "unconnected-(U$6-P4.0{slash}TB0-Pad17)") (class "Default")
      (node (ref "U$6") (pin "17") (pinfunction "P4.0/TB0_17") (pintype "bidirectional"))
    )
    (net (code "81") (name "unconnected-(U$6-P4.1{slash}TB1-Pad18)") (class "Default")
      (node (ref "U$6") (pin "18") (pinfunction "P4.1/TB1_18") (pintype "bidirectional"))
    )
    (net (code "82") (name "unconnected-(U$6-P4.2{slash}TB2-Pad19)") (class "Default")
      (node (ref "U$6") (pin "19") (pinfunction "P4.2/TB2_19") (pintype "bidirectional"))
    )
    (net (code "83") (name "unconnected-(U$6-P4.7{slash}TBCLK-Pad24)") (class "Default")
      (node (ref "U$6") (pin "24") (pinfunction "P4.7/TBCLK_24") (pintype "bidirectional"))
    )
    (net (code "84") (name "unconnected-(U$16-OC-Pad5)") (class "Default")
      (node (ref "U$16") (pin "5") (pinfunction "OC_5") (pintype "bidirectional"))
    )
    (net (code "85") (name "unconnected-(U$17-OC-Pad5)") (class "Default")
      (node (ref "U$17") (pin "5") (pinfunction "OC_5") (pintype "bidirectional"))
    )
    (net (code "86") (name "unconnected-(U$18-OC-Pad5)") (class "Default")
      (node (ref "U$18") (pin "5") (pinfunction "OC_5") (pintype "bidirectional"))
    )
    (net (code "87") (name "unconnected-(U$19-NC1-Pad1)") (class "Default")
      (node (ref "U$19") (pin "1") (pinfunction "NC1_1") (pintype "bidirectional"))
    )
    (net (code "88") (name "unconnected-(U$19-NC2-Pad5)") (class "Default")
      (node (ref "U$19") (pin "5") (pinfunction "NC2_5") (pintype "bidirectional"))
    )
    (net (code "89") (name "unconnected-(U$19-NC3-Pad6)") (class "Default")
      (node (ref "U$19") (pin "6") (pinfunction "NC3_6") (pintype "bidirectional"))
    )
  )
)
